# SparkFunLargeDigitDriver.net
KiCad netlist of a schematic drawn in EAGLE
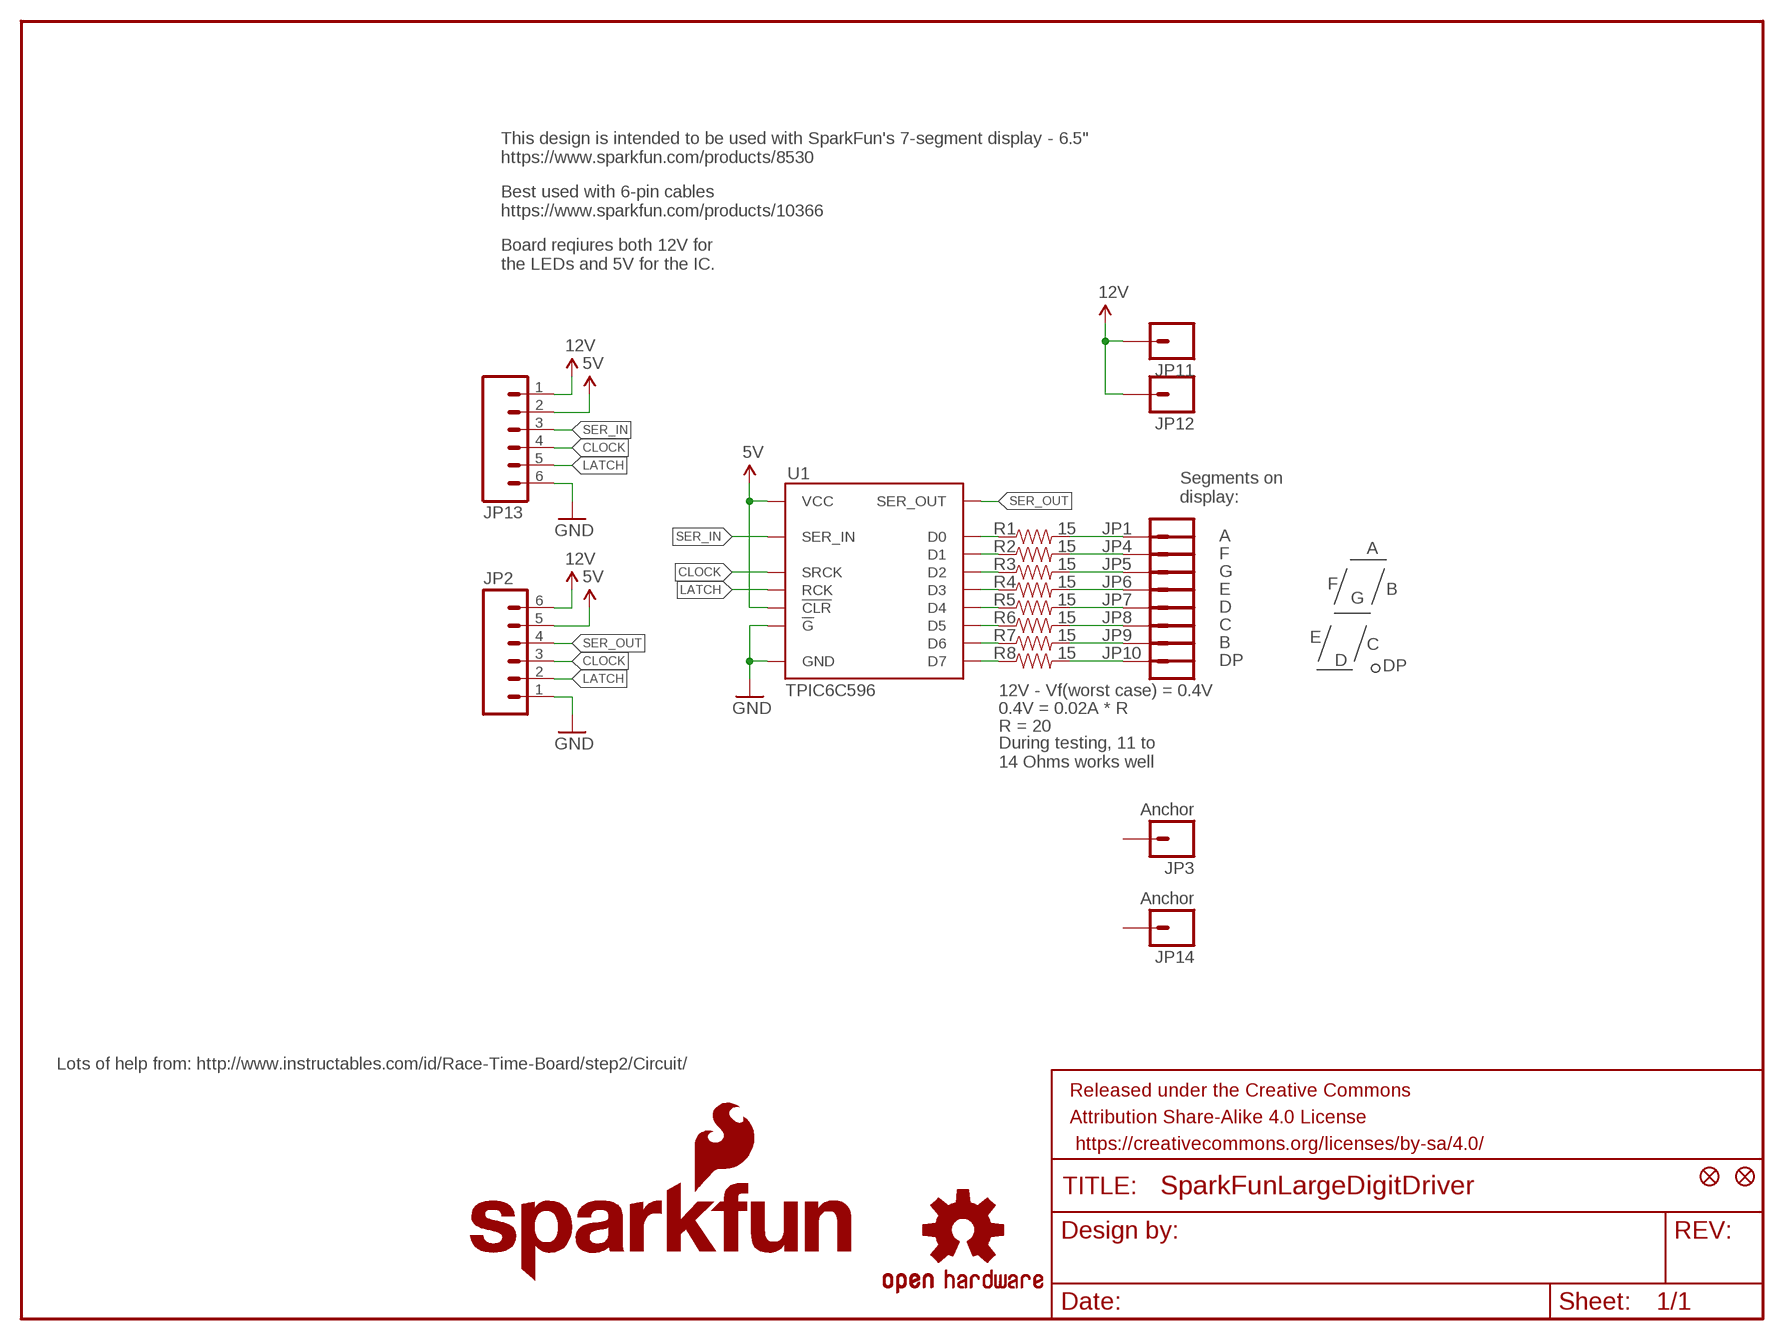
[diagram p0: schematic, sheet 1]

(export (version "E")
  (design (tool "Eeschema 10.0.6"))
  (components
    (comp (ref "FID1")
      (value "FIDUCIAL1X2")
      (footprint "eagle-import:FIDUCIAL-1X2")
      (libsource (lib "eagle-import") (part "FIDUCIAL1X2"))
    )
    (comp (ref "FID2")
      (value "FIDUCIAL1X2")
      (footprint "eagle-import:FIDUCIAL-1X2")
      (libsource (lib "eagle-import") (part "FIDUCIAL1X2"))
    )
    (comp (ref "FRAME1")
      (value "FRAME-LETTER")
      (footprint "eagle-import:CREATIVE_COMMONS")
      (fields (field (name "DESIGNER") "N. Seidle") (field (name "VERSION") "v10"))
      (libsource (lib "eagle-import") (part "FRAME-LETTER"))
    )
    (comp (ref "JP1")
      (value "M01PTH_LONGPAD")
      (footprint "eagle-import:1X01_LONGPAD")
      (libsource (lib "eagle-import") (part "M01PTH_LONGPAD"))
    )
    (comp (ref "JP2")
      (value "M06SMD")
      (footprint "eagle-import:1X06-SMD")
      (libsource (lib "eagle-import") (part "M06SMD"))
    )
    (comp (ref "JP3")
      (value "Anchor")
      (footprint "eagle-import:1X01_LONGPAD")
      (libsource (lib "eagle-import") (part "M01PTH_LONGPAD"))
    )
    (comp (ref "JP4")
      (value "M01PTH_LONGPAD")
      (footprint "eagle-import:1X01_LONGPAD")
      (libsource (lib "eagle-import") (part "M01PTH_LONGPAD"))
    )
    (comp (ref "JP5")
      (value "M01PTH_LONGPAD")
      (footprint "eagle-import:1X01_LONGPAD")
      (libsource (lib "eagle-import") (part "M01PTH_LONGPAD"))
    )
    (comp (ref "JP6")
      (value "M01PTH_LONGPAD")
      (footprint "eagle-import:1X01_LONGPAD")
      (libsource (lib "eagle-import") (part "M01PTH_LONGPAD"))
    )
    (comp (ref "JP7")
      (value "M01PTH_LONGPAD")
      (footprint "eagle-import:1X01_LONGPAD")
      (libsource (lib "eagle-import") (part "M01PTH_LONGPAD"))
    )
    (comp (ref "JP8")
      (value "M01PTH_LONGPAD")
      (footprint "eagle-import:1X01_LONGPAD")
      (libsource (lib "eagle-import") (part "M01PTH_LONGPAD"))
    )
    (comp (ref "JP9")
      (value "M01PTH_LONGPAD")
      (footprint "eagle-import:1X01_LONGPAD")
      (libsource (lib "eagle-import") (part "M01PTH_LONGPAD"))
    )
    (comp (ref "JP10")
      (value "M01PTH_LONGPAD")
      (footprint "eagle-import:1X01_LONGPAD")
      (libsource (lib "eagle-import") (part "M01PTH_LONGPAD"))
    )
    (comp (ref "JP11")
      (value "M01PTH_LONGPAD")
      (footprint "eagle-import:1X01_LONGPAD")
      (libsource (lib "eagle-import") (part "M01PTH_LONGPAD"))
    )
    (comp (ref "JP12")
      (value "M01PTH_LONGPAD")
      (footprint "eagle-import:1X01_LONGPAD")
      (libsource (lib "eagle-import") (part "M01PTH_LONGPAD"))
    )
    (comp (ref "JP13")
      (value "M06SMD")
      (footprint "eagle-import:1X06-SMD")
      (libsource (lib "eagle-import") (part "M06SMD"))
    )
    (comp (ref "JP14")
      (value "Anchor")
      (footprint "eagle-import:1X01_LONGPAD")
      (libsource (lib "eagle-import") (part "M01PTH_LONGPAD"))
    )
    (comp (ref "LOGO1")
      (value "SFE_LOGO_NAME_FLAME.1_INCH")
      (footprint "eagle-import:SFE_LOGO_NAME_FLAME_.1")
      (libsource (lib "eagle-import") (part "SFE_LOGO_NAME_FLAME.1_INCH"))
    )
    (comp (ref "LOGO2")
      (value "OSHW-LOGOS")
      (footprint "eagle-import:OSHW-LOGO-S")
      (libsource (lib "eagle-import") (part "OSHW-LOGOS"))
    )
    (comp (ref "R1")
      (value "15")
      (footprint "eagle-import:0603-RES")
      (libsource (lib "eagle-import") (part "15OHM-1/10W-1%(0603)0603"))
    )
    (comp (ref "R2")
      (value "15")
      (footprint "eagle-import:0603-RES")
      (libsource (lib "eagle-import") (part "15OHM-1/10W-1%(0603)0603"))
    )
    (comp (ref "R3")
      (value "15")
      (footprint "eagle-import:0603-RES")
      (libsource (lib "eagle-import") (part "15OHM-1/10W-1%(0603)0603"))
    )
    (comp (ref "R4")
      (value "15")
      (footprint "eagle-import:0603-RES")
      (libsource (lib "eagle-import") (part "15OHM-1/10W-1%(0603)0603"))
    )
    (comp (ref "R5")
      (value "15")
      (footprint "eagle-import:0603-RES")
      (libsource (lib "eagle-import") (part "15OHM-1/10W-1%(0603)0603"))
    )
    (comp (ref "R6")
      (value "15")
      (footprint "eagle-import:0603-RES")
      (libsource (lib "eagle-import") (part "15OHM-1/10W-1%(0603)0603"))
    )
    (comp (ref "R7")
      (value "15")
      (footprint "eagle-import:0603-RES")
      (libsource (lib "eagle-import") (part "15OHM-1/10W-1%(0603)0603"))
    )
    (comp (ref "R8")
      (value "15")
      (footprint "eagle-import:0603-RES")
      (libsource (lib "eagle-import") (part "15OHM-1/10W-1%(0603)0603"))
    )
    (comp (ref "U1")
      (value "TPIC6C596")
      (footprint "eagle-import:SO016")
      (libsource (lib "eagle-import") (part "TPIC6C596SOIC"))
    )
  )
  (nets
    (net (code "1") (name "5V") (class "Default")
      (node (ref "JP13") (pin "2") (pinfunction "2_2") (pintype "passive"))
      (node (ref "JP2") (pin "5") (pinfunction "5_5") (pintype "passive"))
      (node (ref "U1") (pin "1") (pinfunction "VCC_1") (pintype "power_in"))
      (node (ref "U1") (pin "7") (pinfunction "~{CLR}_7") (pintype "input"))
    )
    (net (code "2") (name "12V") (class "Default")
      (node (ref "JP11") (pin "1") (pinfunction "1_1") (pintype "passive"))
      (node (ref "JP12") (pin "1") (pinfunction "1_1") (pintype "passive"))
      (node (ref "JP13") (pin "1") (pinfunction "1_1") (pintype "passive"))
      (node (ref "JP2") (pin "6") (pinfunction "6_6") (pintype "passive"))
    )
    (net (code "3") (name "CLOCK") (class "Default")
      (node (ref "JP13") (pin "4") (pinfunction "4_4") (pintype "passive"))
      (node (ref "JP2") (pin "3") (pinfunction "3_3") (pintype "passive"))
      (node (ref "U1") (pin "15") (pinfunction "SRCK_15") (pintype "input"))
    )
    (net (code "4") (name "GND") (class "Default")
      (node (ref "JP13") (pin "6") (pinfunction "6_6") (pintype "passive"))
      (node (ref "JP2") (pin "1") (pinfunction "1_1") (pintype "passive"))
      (node (ref "U1") (pin "16") (pinfunction "GND_16") (pintype "power_in"))
      (node (ref "U1") (pin "8") (pinfunction "~{G}_8") (pintype "input"))
    )
    (net (code "5") (name "LATCH") (class "Default")
      (node (ref "JP13") (pin "5") (pinfunction "5_5") (pintype "passive"))
      (node (ref "JP2") (pin "2") (pinfunction "2_2") (pintype "passive"))
      (node (ref "U1") (pin "10") (pinfunction "RCK_10") (pintype "input"))
    )
    (net (code "6") (name "Net-(JP1-Pad1)") (class "Default")
      (node (ref "JP1") (pin "1") (pinfunction "1_1") (pintype "passive"))
      (node (ref "R1") (pin "2") (pinfunction "2_2") (pintype "passive"))
    )
    (net (code "7") (name "Net-(JP4-Pad1)") (class "Default")
      (node (ref "JP4") (pin "1") (pinfunction "1_1") (pintype "passive"))
      (node (ref "R2") (pin "2") (pinfunction "2_2") (pintype "passive"))
    )
    (net (code "8") (name "Net-(JP5-Pad1)") (class "Default")
      (node (ref "JP5") (pin "1") (pinfunction "1_1") (pintype "passive"))
      (node (ref "R3") (pin "2") (pinfunction "2_2") (pintype "passive"))
    )
    (net (code "9") (name "Net-(JP6-Pad1)") (class "Default")
      (node (ref "JP6") (pin "1") (pinfunction "1_1") (pintype "passive"))
      (node (ref "R4") (pin "2") (pinfunction "2_2") (pintype "passive"))
    )
    (net (code "10") (name "Net-(JP7-Pad1)") (class "Default")
      (node (ref "JP7") (pin "1") (pinfunction "1_1") (pintype "passive"))
      (node (ref "R5") (pin "2") (pinfunction "2_2") (pintype "passive"))
    )
    (net (code "11") (name "Net-(JP8-Pad1)") (class "Default")
      (node (ref "JP8") (pin "1") (pinfunction "1_1") (pintype "passive"))
      (node (ref "R6") (pin "2") (pinfunction "2_2") (pintype "passive"))
    )
    (net (code "12") (name "Net-(JP9-Pad1)") (class "Default")
      (node (ref "JP9") (pin "1") (pinfunction "1_1") (pintype "passive"))
      (node (ref "R7") (pin "2") (pinfunction "2_2") (pintype "passive"))
    )
    (net (code "13") (name "Net-(JP10-Pad1)") (class "Default")
      (node (ref "JP10") (pin "1") (pinfunction "1_1") (pintype "passive"))
      (node (ref "R8") (pin "2") (pinfunction "2_2") (pintype "passive"))
    )
    (net (code "14") (name "Net-(U1-D0)") (class "Default")
      (node (ref "R1") (pin "1") (pinfunction "1_1") (pintype "passive"))
      (node (ref "U1") (pin "3") (pinfunction "D0_3") (pintype "output"))
    )
    (net (code "15") (name "Net-(U1-D1)") (class "Default")
      (node (ref "R2") (pin "1") (pinfunction "1_1") (pintype "passive"))
      (node (ref "U1") (pin "4") (pinfunction "D1_4") (pintype "output"))
    )
    (net (code "16") (name "Net-(U1-D2)") (class "Default")
      (node (ref "R3") (pin "1") (pinfunction "1_1") (pintype "passive"))
      (node (ref "U1") (pin "5") (pinfunction "D2_5") (pintype "output"))
    )
    (net (code "17") (name "Net-(U1-D3)") (class "Default")
      (node (ref "R4") (pin "1") (pinfunction "1_1") (pintype "passive"))
      (node (ref "U1") (pin "6") (pinfunction "D3_6") (pintype "output"))
    )
    (net (code "18") (name "Net-(U1-D4)") (class "Default")
      (node (ref "R5") (pin "1") (pinfunction "1_1") (pintype "passive"))
      (node (ref "U1") (pin "11") (pinfunction "D4_11") (pintype "output"))
    )
    (net (code "19") (name "Net-(U1-D5)") (class "Default")
      (node (ref "R6") (pin "1") (pinfunction "1_1") (pintype "passive"))
      (node (ref "U1") (pin "12") (pinfunction "D5_12") (pintype "output"))
    )
    (net (code "20") (name "Net-(U1-D6)") (class "Default")
      (node (ref "R7") (pin "1") (pinfunction "1_1") (pintype "passive"))
      (node (ref "U1") (pin "13") (pinfunction "D6_13") (pintype "output"))
    )
    (net (code "21") (name "Net-(U1-D7)") (class "Default")
      (node (ref "R8") (pin "1") (pinfunction "1_1") (pintype "passive"))
      (node (ref "U1") (pin "14") (pinfunction "D7_14") (pintype "output"))
    )
    (net (code "22") (name "SER_IN") (class "Default")
      (node (ref "JP13") (pin "3") (pinfunction "3_3") (pintype "passive"))
      (node (ref "U1") (pin "2") (pinfunction "SER_IN_2") (pintype "input"))
    )
    (net (code "23") (name "SER_OUT") (class "Default")
      (node (ref "JP2") (pin "4") (pinfunction "4_4") (pintype "passive"))
      (node (ref "U1") (pin "9") (pinfunction "SER_OUT_9") (pintype "output"))
    )
    (net (code "24") (name "unconnected-(JP3-Pad1)") (class "Default")
      (node (ref "JP3") (pin "1") (pinfunction "1_1") (pintype "passive"))
    )
    (net (code "25") (name "unconnected-(JP14-Pad1)") (class "Default")
      (node (ref "JP14") (pin "1") (pinfunction "1_1") (pintype "passive"))
    )
  )
)
